# STEP-UP.net
KiCad netlist of a schematic drawn in Altium Designer
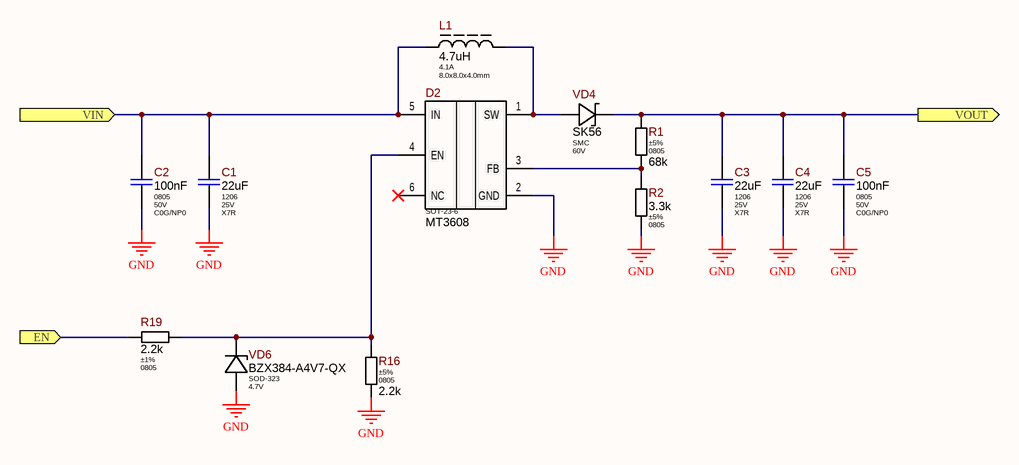
[diagram p0: STEP-UP.SchDoc]

(export (version "E")
  (design (tool "Eeschema 10.0.6"))
  (components
    (comp (ref "C1")
      (value "22uF")
      (footprint "C_CERAMIC_1206_MED")
      (description "22uF 25V")
      (fields
        (field (name "PACKAGE") "1206")
        (field (name "VOLTAGE") "25V")
        (field (name "DIELECTRIC TYPE") "X7R")
        (field (name "PART NUMBER") "CL31A226KAHNNNE")
        (field (name "MANUFACTURER") "SAMSUNG")
      )
      (libsource (lib "vitech_capacitors") (part "1206B102K102CG"))
    )
    (comp (ref "C2")
      (value "100nF")
      (footprint "C_CERAMIC_0805_HI")
      (fields
        (field (name "PART NUMBER") "**")
        (field (name "MANUFACTURER") "Hitano")
        (field (name "TOLERANCE") "±5%")
        (field (name "PACKAGE") "0805")
        (field (name "VOLTAGE") "50V")
        (field (name "DIELECTRIC TYPE") "C0G/NP0")
      )
      (libsource (lib "vitech_capacitors") (part "CERAMIC_0805"))
    )
    (comp (ref "C3")
      (value "22uF")
      (footprint "C_CERAMIC_1206_MED")
      (description "22uF 25V")
      (fields
        (field (name "PACKAGE") "1206")
        (field (name "VOLTAGE") "25V")
        (field (name "DIELECTRIC TYPE") "X7R")
        (field (name "PART NUMBER") "CL31A226KAHNNNE")
        (field (name "MANUFACTURER") "SAMSUNG")
      )
      (libsource (lib "vitech_capacitors") (part "1206B102K102CG"))
    )
    (comp (ref "C4")
      (value "22uF")
      (footprint "C_CERAMIC_1206_MED")
      (description "22uF 25V")
      (fields
        (field (name "PACKAGE") "1206")
        (field (name "VOLTAGE") "25V")
        (field (name "DIELECTRIC TYPE") "X7R")
        (field (name "PART NUMBER") "CL31A226KAHNNNE")
        (field (name "MANUFACTURER") "SAMSUNG")
      )
      (libsource (lib "vitech_capacitors") (part "1206B102K102CG"))
    )
    (comp (ref "C5")
      (value "100nF")
      (footprint "C_CERAMIC_0805_HI")
      (fields
        (field (name "PART NUMBER") "**")
        (field (name "MANUFACTURER") "Hitano")
        (field (name "TOLERANCE") "±5%")
        (field (name "PACKAGE") "0805")
        (field (name "VOLTAGE") "50V")
        (field (name "DIELECTRIC TYPE") "C0G/NP0")
      )
      (libsource (lib "vitech_capacitors") (part "CERAMIC_0805"))
    )
    (comp (ref "D2")
      (value "MT3608")
      (footprint "MT3608_MED")
      (description "2V-24V Input High Efficiency 1.2MHz 2A Step Up Converter")
      (fields
        (field (name "PACKAGE") "SOT-23-6")
        (field (name "PART NUMBER") "MT3608")
        (field (name "MANUFACTURER") "Aerosemi")
      )
      (libsource (lib "ic") (part "MT3608"))
    )
    (comp (ref "L1")
      (value "4.7uH")
      (footprint "SWPA8040S-Series")
      (description "4.7uH Magnetic-Resin Shielded Wirewound Inductor 4.1 A 25mOhm Max")
      (fields
        (field (name "CURRENT") "4.1A")
        (field (name "PACKAGE") "8.0x8.0x4.0mm")
        (field (name "PART NUMBER") "SWPA8040S4R7NT")
        (field (name "TOLERANCE") "±30%")
      )
      (libsource (lib "inductors") (part "SWPA8040S4R7NT"))
    )
    (comp (ref "R1")
      (value "68k")
      (footprint "R_ANY_CHIP_0805_MED")
      (description "2.2 kOhms ±5% 1/8W 0805 Thick Film Resistor")
      (fields
        (field (name "TOLERANCE") "±5%")
        (field (name "PACKAGE") "0805")
        (field (name "PART NUMBER") "RC0805JR-072K2L")
        (field (name "MANUFACTURER") "Yageo")
      )
      (libsource (lib "resistors") (part "RC0805JR-072K2L"))
    )
    (comp (ref "R2")
      (value "3.3k")
      (footprint "R_ANY_CHIP_0805_MED")
      (description "3.3 kOhms ±5%, 1/8W 0805 Thick Film Resistor")
      (fields
        (field (name "TOLERANCE") "±5%")
        (field (name "PACKAGE") "0805")
        (field (name "PART NUMBER") "RC0805JR-073K3L")
        (field (name "MANUFACTURER") "Yageo")
      )
      (libsource (lib "resistors") (part "RC0805JR-073K3L"))
    )
    (comp (ref "R16")
      (value "2.2k")
      (footprint "R_ANY_CHIP_0805_MED")
      (description "2.2 kOhms ±5% 1/8W 0805 Thick Film Resistor")
      (fields
        (field (name "TOLERANCE") "±5%")
        (field (name "PACKAGE") "0805")
        (field (name "PART NUMBER") "RC0805JR-072K2L")
        (field (name "MANUFACTURER") "Yageo")
      )
      (libsource (lib "resistors") (part "RC0805JR-072K2L"))
    )
    (comp (ref "R19")
      (value "2.2k")
      (footprint "R_ANY_CHIP_0805_MED")
      (description "2.2 kOhms ±1% 1/8W 0805 Thick Film Resistor")
      (fields
        (field (name "TOLERANCE") "±1%")
        (field (name "PACKAGE") "0805")
        (field (name "PART NUMBER") "RC0805FR-072K2L")
        (field (name "MANUFACTURER") "Yageo")
      )
      (libsource (lib "resistors") (part "RC0805FR-072K2L"))
    )
    (comp (ref "VD4")
      (value "SK56")
      (footprint "SMC")
      (description "Diode Schottky 60V 5A, SMC")
      (fields
        (field (name "PART NUMBER") "SK56")
        (field (name "PACKAGE") "SMC")
        (field (name "VOLTAGE") "60V")
        (field (name "MANUFACTURER") "KLS")
      )
      (libsource (lib "vitech_semiconductors") (part "SS34"))
    )
    (comp (ref "VD6")
      (value "BZX384-A4V7-QX")
      (footprint "SOD-323_MED")
      (description "Zener Diode 4.7V, 300mW, ±1%, Leakage 3uA @ 2V, SOD-323")
      (fields
        (field (name "PART NUMBER") "BZX384-A4V7-QX")
        (field (name "PACKAGE") "SOD-323")
        (field (name "VOLTAGE") "4.7V")
        (field (name "MANUFACTURER") "Nexperia USA")
      )
      (libsource (lib "vitech_semiconductors") (part "BZX384-A4V7-QX"))
    )
  )
  (nets
    (net (code "1") (name "/EN") (class "Default") (node (ref "R19") (pin "1") (pintype "passive")))
    (net (code "2") (name "/VIN") (class "Default")
      (node (ref "C1") (pin "1") (pinfunction "1_1") (pintype "passive"))
      (node (ref "C2") (pin "1") (pinfunction "1_1") (pintype "passive"))
      (node (ref "D2") (pin "5") (pinfunction "IN_5") (pintype "passive"))
      (node (ref "L1") (pin "1") (pintype "passive"))
    )
    (net (code "3") (name "/VOUT") (class "Default")
      (node (ref "C3") (pin "1") (pinfunction "1_1") (pintype "passive"))
      (node (ref "C4") (pin "1") (pinfunction "1_1") (pintype "passive"))
      (node (ref "C5") (pin "1") (pinfunction "1_1") (pintype "passive"))
      (node (ref "R1") (pin "1") (pintype "passive"))
      (node (ref "VD4") (pin "CA") (pintype "passive"))
    )
    (net (code "4") (name "GND") (class "Default")
      (node (ref "C1") (pin "2") (pinfunction "2_2") (pintype "passive"))
      (node (ref "C2") (pin "2") (pinfunction "2_2") (pintype "passive"))
      (node (ref "C3") (pin "2") (pinfunction "2_2") (pintype "passive"))
      (node (ref "C4") (pin "2") (pinfunction "2_2") (pintype "passive"))
      (node (ref "C5") (pin "2") (pinfunction "2_2") (pintype "passive"))
      (node (ref "D2") (pin "2") (pinfunction "GND_2") (pintype "passive"))
      (node (ref "R16") (pin "2") (pintype "passive"))
      (node (ref "R2") (pin "2") (pintype "passive"))
      (node (ref "VD6") (pin "AN") (pintype "passive"))
    )
    (net (code "5") (name "Net-(D2-EN)") (class "Default")
      (node (ref "D2") (pin "4") (pinfunction "EN_4") (pintype "passive"))
      (node (ref "R16") (pin "1") (pintype "passive"))
      (node (ref "R19") (pin "2") (pintype "passive"))
      (node (ref "VD6") (pin "CA") (pintype "passive"))
    )
    (net (code "6") (name "Net-(D2-FB)") (class "Default")
      (node (ref "D2") (pin "3") (pinfunction "FB_3") (pintype "passive"))
      (node (ref "R1") (pin "2") (pintype "passive"))
      (node (ref "R2") (pin "1") (pintype "passive"))
    )
    (net (code "7") (name "Net-(D2-SW)") (class "Default")
      (node (ref "D2") (pin "1") (pinfunction "SW_1") (pintype "passive"))
      (node (ref "L1") (pin "2") (pintype "passive"))
      (node (ref "VD4") (pin "AN") (pintype "passive"))
    )
    (net (code "8") (name "unconnected-(D2-NC-Pad6)") (class "Default")
      (node (ref "D2") (pin "6") (pinfunction "NC_6") (pintype "passive+no_connect"))
    )
  )
)
